# 90_51_4.net
KiCad netlist of a schematic drawn in Altium Designer
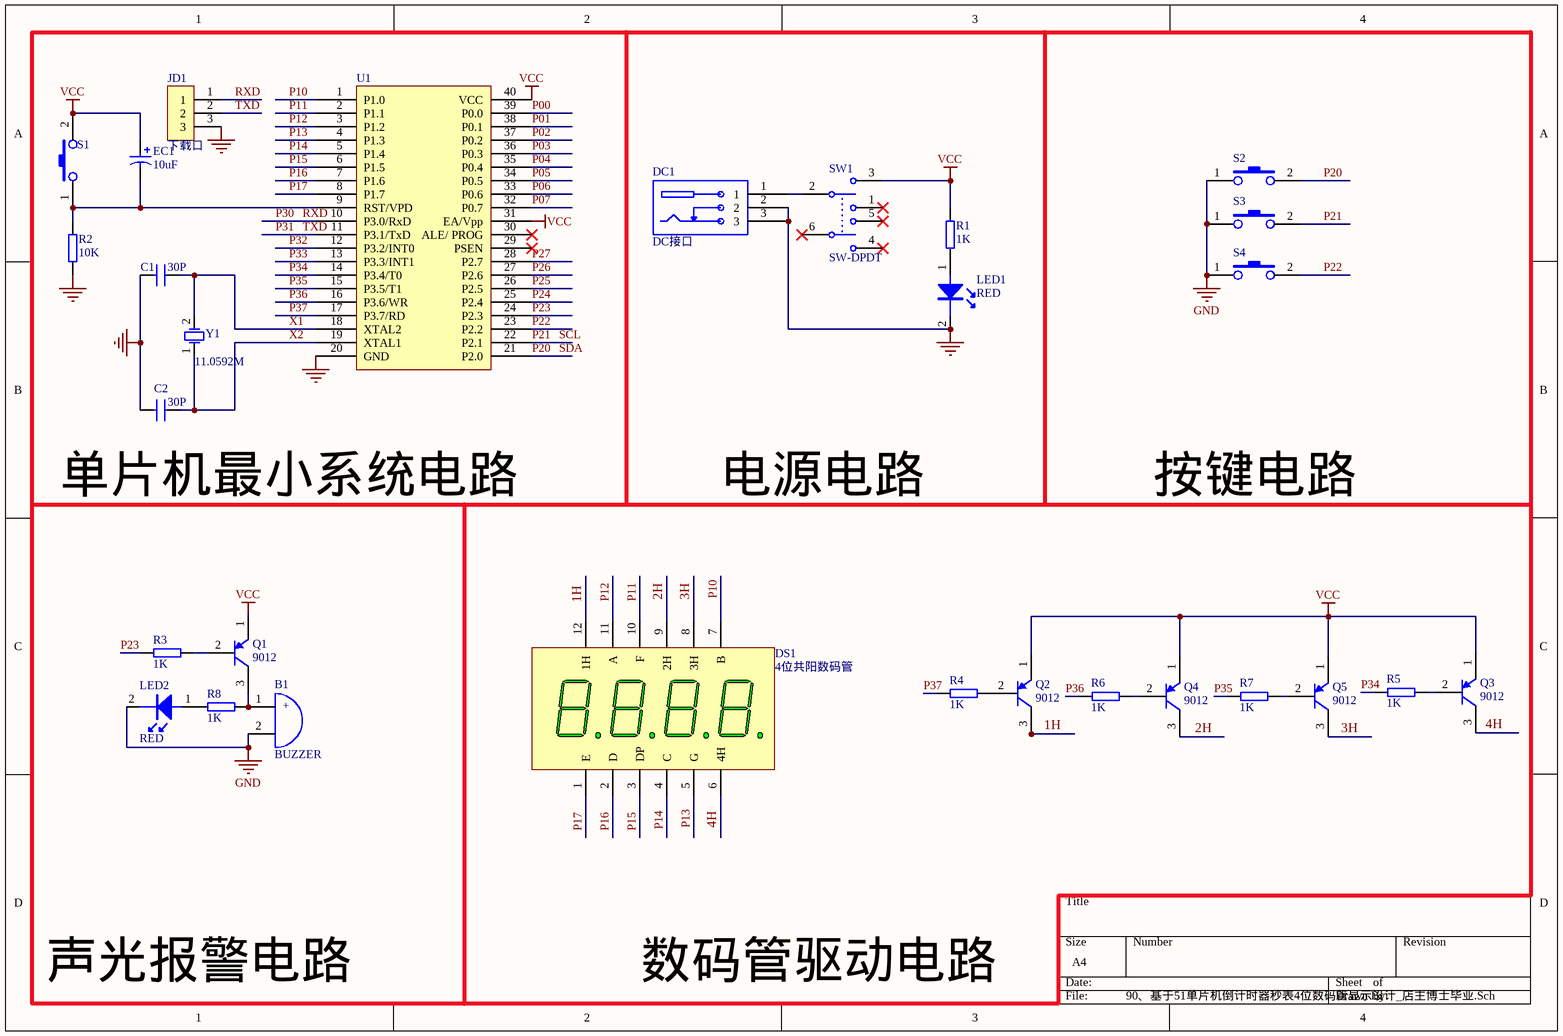
[diagram p0: 90、基于51单片机倒计时器秒表4位数码管显示设计_店主博士毕业.SchDoc]

(export (version "E")
  (design (tool "Eeschema 10.0.6"))
  (components
    (comp (ref "B1")
      (value "BUZZER")
      (footprint "BUZZERSOT_PLASTIC")
      (description "蜂鸣器")
      (libsource (lib "参考") (part "BUZZER"))
    )
    (comp (ref "C1")
      (value "30P")
      (footprint "RAD-0.1")
      (description "无极性电容")
      (libsource (lib "参考") (part "CAP"))
    )
    (comp (ref "C2")
      (value "30P")
      (footprint "RAD-0.1")
      (description "无极性电容")
      (libsource (lib "参考") (part "CAP"))
    )
    (comp (ref "DC1")
      (value "DC接口")
      (footprint "DC-JACK-002")
      (description "DC接口（分大小）")
      (libsource (lib "参考") (part "DC接口"))
    )
    (comp (ref "DS1") (value "4位共阳数码管") (footprint "SEG3641") (libsource (lib "参考") (part "4位共阳数码管")))
    (comp (ref "EC1")
      (value "10uF")
      (footprint "RB.1/.2")
      (description "极性电容")
      (libsource (lib "参考") (part "CAP_EC"))
    )
    (comp (ref "JD1")
      (value "下载口")
      (footprint "下载串口")
      (description "下载口2.54排针")
      (libsource (lib "参考") (part "下载口"))
    )
    (comp (ref "LED1")
      (value "RED")
      (footprint "LED_D3MM12")
      (description "LED灯")
      (libsource (lib "参考") (part "LED"))
    )
    (comp (ref "LED2")
      (value "RED")
      (footprint "LED_D3MM12")
      (description "LED灯")
      (libsource (lib "参考") (part "LED"))
    )
    (comp (ref "Q1")
      (value "9012")
      (footprint "TO-92")
      (description "直插三极管")
      (libsource (lib "参考") (part "9012"))
    )
    (comp (ref "Q2")
      (value "9012")
      (footprint "TO-92")
      (description "直插三极管")
      (libsource (lib "参考") (part "9012"))
    )
    (comp (ref "Q3")
      (value "9012")
      (footprint "TO-92")
      (description "直插三极管")
      (libsource (lib "参考") (part "9012"))
    )
    (comp (ref "Q4")
      (value "9012")
      (footprint "TO-92")
      (description "直插三极管")
      (libsource (lib "参考") (part "9012"))
    )
    (comp (ref "Q5")
      (value "9012")
      (footprint "TO-92")
      (description "直插三极管")
      (libsource (lib "参考") (part "9012"))
    )
    (comp (ref "R1")
      (value "1K")
      (footprint "AXIAL0.3")
      (description "电阻")
      (libsource (lib "参考") (part "RES"))
    )
    (comp (ref "R2")
      (value "10K")
      (footprint "AXIAL0.3")
      (description "电阻")
      (libsource (lib "参考") (part "RES"))
    )
    (comp (ref "R3")
      (value "1K")
      (footprint "AXIAL0.3")
      (description "电阻")
      (libsource (lib "参考") (part "RES"))
    )
    (comp (ref "R4")
      (value "1K")
      (footprint "AXIAL0.3")
      (description "电阻")
      (libsource (lib "参考") (part "RES"))
    )
    (comp (ref "R5")
      (value "1K")
      (footprint "AXIAL0.3")
      (description "电阻")
      (libsource (lib "参考") (part "RES"))
    )
    (comp (ref "R6")
      (value "1K")
      (footprint "AXIAL0.3")
      (description "电阻")
      (libsource (lib "参考") (part "RES"))
    )
    (comp (ref "R7")
      (value "1K")
      (footprint "AXIAL0.3")
      (description "电阻")
      (libsource (lib "参考") (part "RES"))
    )
    (comp (ref "R8")
      (value "1K")
      (footprint "AXIAL0.3")
      (description "电阻")
      (libsource (lib "参考") (part "RES"))
    )
    (comp (ref "S1")
      (value "BUTTOM")
      (footprint "BUTTOM_6x6DIP")
      (description "按键")
      (libsource (lib "参考") (part "BUTTOM"))
    )
    (comp (ref "S2")
      (value "BUTTOM")
      (footprint "BUTTOM_6x6DIP")
      (description "按键")
      (libsource (lib "参考") (part "BUTTOM"))
    )
    (comp (ref "S3")
      (value "BUTTOM")
      (footprint "BUTTOM_6x6DIP")
      (description "按键")
      (libsource (lib "参考") (part "BUTTOM"))
    )
    (comp (ref "S4")
      (value "BUTTOM")
      (footprint "BUTTOM_6x6DIP")
      (description "按键")
      (libsource (lib "参考") (part "BUTTOM"))
    )
    (comp (ref "SW1")
      (value "SW-DPDT")
      (footprint "SW")
      (description "电源开关")
      (fields (field (name "PUBLISHER") "Altium Limited"))
      (libsource (lib "参考") (part "SW-DPDT"))
    )
    (comp (ref "U1")
      (value "STC89C52")
      (footprint "STC89")
      (description "51单片机")
      (libsource (lib "参考") (part "STC51"))
    )
    (comp (ref "Y1")
      (value "11.0592M")
      (footprint "X_HC-49")
      (description "晶振")
      (libsource (lib "参考") (part "XTAL DIP"))
    )
  )
  (nets
    (net (code "1") (name "/1H") (class "Default")
      (node (ref "DS1") (pin "12") (pinfunction "1H_12") (pintype "passive"))
      (node (ref "Q2") (pin "3") (pinfunction "c_3") (pintype "passive"))
    )
    (net (code "2") (name "/2H") (class "Default")
      (node (ref "DS1") (pin "9") (pinfunction "2H_9") (pintype "passive"))
      (node (ref "Q4") (pin "3") (pinfunction "c_3") (pintype "passive"))
    )
    (net (code "3") (name "/3H") (class "Default")
      (node (ref "DS1") (pin "8") (pinfunction "3H_8") (pintype "passive"))
      (node (ref "Q5") (pin "3") (pinfunction "c_3") (pintype "passive"))
    )
    (net (code "4") (name "/4H") (class "Default")
      (node (ref "DS1") (pin "6") (pinfunction "4H_6") (pintype "passive"))
      (node (ref "Q3") (pin "3") (pinfunction "c_3") (pintype "passive"))
    )
    (net (code "5") (name "/P00") (class "Default")
      (node (ref "U1") (pin "39") (pinfunction "P0.0_39") (pintype "passive"))
    )
    (net (code "6") (name "/P01") (class "Default")
      (node (ref "U1") (pin "38") (pinfunction "P0.1_38") (pintype "passive"))
    )
    (net (code "7") (name "/P02") (class "Default")
      (node (ref "U1") (pin "37") (pinfunction "P0.2_37") (pintype "passive"))
    )
    (net (code "8") (name "/P03") (class "Default")
      (node (ref "U1") (pin "36") (pinfunction "P0.3_36") (pintype "passive"))
    )
    (net (code "9") (name "/P04") (class "Default")
      (node (ref "U1") (pin "35") (pinfunction "P0.4_35") (pintype "passive"))
    )
    (net (code "10") (name "/P05") (class "Default")
      (node (ref "U1") (pin "34") (pinfunction "P0.5_34") (pintype "passive"))
    )
    (net (code "11") (name "/P06") (class "Default")
      (node (ref "U1") (pin "33") (pinfunction "P0.6_33") (pintype "passive"))
    )
    (net (code "12") (name "/P07") (class "Default")
      (node (ref "U1") (pin "32") (pinfunction "P0.7_32") (pintype "passive"))
    )
    (net (code "13") (name "/P10") (class "Default")
      (node (ref "DS1") (pin "7") (pinfunction "B_7") (pintype "passive"))
      (node (ref "U1") (pin "1") (pinfunction "P1.0_1") (pintype "passive"))
    )
    (net (code "14") (name "/P11") (class "Default")
      (node (ref "DS1") (pin "10") (pinfunction "F_10") (pintype "passive"))
      (node (ref "U1") (pin "2") (pinfunction "P1.1_2") (pintype "passive"))
    )
    (net (code "15") (name "/P12") (class "Default")
      (node (ref "DS1") (pin "11") (pinfunction "A_11") (pintype "passive"))
      (node (ref "U1") (pin "3") (pinfunction "P1.2_3") (pintype "passive"))
    )
    (net (code "16") (name "/P13") (class "Default")
      (node (ref "DS1") (pin "5") (pinfunction "G_5") (pintype "passive"))
      (node (ref "U1") (pin "4") (pinfunction "P1.3_4") (pintype "passive"))
    )
    (net (code "17") (name "/P14") (class "Default")
      (node (ref "DS1") (pin "4") (pinfunction "C_4") (pintype "passive"))
      (node (ref "U1") (pin "5") (pinfunction "P1.4_5") (pintype "passive"))
    )
    (net (code "18") (name "/P15") (class "Default")
      (node (ref "DS1") (pin "3") (pinfunction "DP_3") (pintype "passive"))
      (node (ref "U1") (pin "6") (pinfunction "P1.5_6") (pintype "passive"))
    )
    (net (code "19") (name "/P16") (class "Default")
      (node (ref "DS1") (pin "2") (pinfunction "D_2") (pintype "passive"))
      (node (ref "U1") (pin "7") (pinfunction "P1.6_7") (pintype "passive"))
    )
    (net (code "20") (name "/P17") (class "Default")
      (node (ref "DS1") (pin "1") (pinfunction "E_1") (pintype "passive"))
      (node (ref "U1") (pin "8") (pinfunction "P1.7_8") (pintype "passive"))
    )
    (net (code "21") (name "/P20") (class "Default")
      (node (ref "S2") (pin "2") (pinfunction "2_2") (pintype "passive"))
      (node (ref "U1") (pin "21") (pinfunction "P2.0_21") (pintype "passive"))
    )
    (net (code "22") (name "/P21") (class "Default")
      (node (ref "S3") (pin "2") (pinfunction "2_2") (pintype "passive"))
      (node (ref "U1") (pin "22") (pinfunction "P2.1_22") (pintype "passive"))
    )
    (net (code "23") (name "/P22") (class "Default")
      (node (ref "S4") (pin "2") (pinfunction "2_2") (pintype "passive"))
      (node (ref "U1") (pin "23") (pinfunction "P2.2_23") (pintype "passive"))
    )
    (net (code "24") (name "/P23") (class "Default")
      (node (ref "R3") (pin "2") (pinfunction "2_2") (pintype "passive"))
      (node (ref "U1") (pin "24") (pinfunction "P2.3_24") (pintype "passive"))
    )
    (net (code "25") (name "/P24") (class "Default")
      (node (ref "U1") (pin "25") (pinfunction "P2.4_25") (pintype "passive"))
    )
    (net (code "26") (name "/P25") (class "Default")
      (node (ref "U1") (pin "26") (pinfunction "P2.5_26") (pintype "passive"))
    )
    (net (code "27") (name "/P26") (class "Default")
      (node (ref "U1") (pin "27") (pinfunction "P2.6_27") (pintype "passive"))
    )
    (net (code "28") (name "/P27") (class "Default")
      (node (ref "U1") (pin "28") (pinfunction "P2.7_28") (pintype "passive"))
    )
    (net (code "29") (name "/P30") (class "Default")
      (node (ref "JD1") (pin "1") (pinfunction "1_1") (pintype "passive"))
      (node (ref "U1") (pin "10") (pinfunction "P3.0/RxD_10") (pintype "passive"))
    )
    (net (code "30") (name "/P31") (class "Default")
      (node (ref "JD1") (pin "2") (pinfunction "2_2") (pintype "passive"))
      (node (ref "U1") (pin "11") (pinfunction "P3.1/TxD_11") (pintype "passive"))
    )
    (net (code "31") (name "/P32") (class "Default")
      (node (ref "U1") (pin "12") (pinfunction "P3.2/INT0_12") (pintype "passive"))
    )
    (net (code "32") (name "/P33") (class "Default")
      (node (ref "U1") (pin "13") (pinfunction "P3.3/INT1_13") (pintype "passive"))
    )
    (net (code "33") (name "/P34") (class "Default")
      (node (ref "R5") (pin "2") (pinfunction "2_2") (pintype "passive"))
      (node (ref "U1") (pin "14") (pinfunction "P3.4/T0_14") (pintype "passive"))
    )
    (net (code "34") (name "/P35") (class "Default")
      (node (ref "R7") (pin "2") (pinfunction "2_2") (pintype "passive"))
      (node (ref "U1") (pin "15") (pinfunction "P3.5/T1_15") (pintype "passive"))
    )
    (net (code "35") (name "/P36") (class "Default")
      (node (ref "R6") (pin "2") (pinfunction "2_2") (pintype "passive"))
      (node (ref "U1") (pin "16") (pinfunction "P3.6/WR_16") (pintype "passive"))
    )
    (net (code "36") (name "/P37") (class "Default")
      (node (ref "R4") (pin "2") (pinfunction "2_2") (pintype "passive"))
      (node (ref "U1") (pin "17") (pinfunction "P3.7/RD_17") (pintype "passive"))
    )
    (net (code "37") (name "/X1") (class "Default")
      (node (ref "C1") (pin "2") (pinfunction "2_2") (pintype "passive"))
      (node (ref "U1") (pin "18") (pinfunction "XTAL2_18") (pintype "passive"))
      (node (ref "Y1") (pin "2") (pinfunction "OSC2_2") (pintype "passive"))
    )
    (net (code "38") (name "/X2") (class "Default")
      (node (ref "C2") (pin "2") (pinfunction "2_2") (pintype "passive"))
      (node (ref "U1") (pin "19") (pinfunction "XTAL1_19") (pintype "passive"))
      (node (ref "Y1") (pin "1") (pinfunction "OSC1_1") (pintype "passive"))
    )
    (net (code "39") (name "GND") (class "Default")
      (node (ref "B1") (pin "2") (pinfunction "2_2") (pintype "passive"))
      (node (ref "C1") (pin "1") (pinfunction "1_1") (pintype "passive"))
      (node (ref "C2") (pin "1") (pinfunction "1_1") (pintype "passive"))
      (node (ref "DC1") (pin "2") (pinfunction "2_2") (pintype "passive"))
      (node (ref "DC1") (pin "3") (pinfunction "3_3") (pintype "passive"))
      (node (ref "JD1") (pin "3") (pinfunction "3_3") (pintype "passive"))
      (node (ref "LED1") (pin "2") (pinfunction "2_2") (pintype "passive"))
      (node (ref "LED2") (pin "2") (pinfunction "2_2") (pintype "passive"))
      (node (ref "R2") (pin "1") (pinfunction "1_1") (pintype "passive"))
      (node (ref "S2") (pin "1") (pinfunction "1_1") (pintype "passive"))
      (node (ref "S3") (pin "1") (pinfunction "1_1") (pintype "passive"))
      (node (ref "S4") (pin "1") (pinfunction "1_1") (pintype "passive"))
      (node (ref "U1") (pin "20") (pinfunction "GND_20") (pintype "passive"))
    )
    (net (code "40") (name "Net-(DC1-Pad1)") (class "Default")
      (node (ref "DC1") (pin "1") (pinfunction "1_1") (pintype "passive"))
      (node (ref "SW1") (pin "2") (pinfunction "2_2") (pintype "passive"))
    )
    (net (code "41") (name "Net-(LED1-Pad1)") (class "Default")
      (node (ref "LED1") (pin "1") (pinfunction "1_1") (pintype "passive"))
      (node (ref "R1") (pin "1") (pinfunction "1_1") (pintype "passive"))
    )
    (net (code "42") (name "Net-(LED2-Pad1)") (class "Default")
      (node (ref "LED2") (pin "1") (pinfunction "1_1") (pintype "passive"))
      (node (ref "R8") (pin "1") (pinfunction "1_1") (pintype "passive"))
    )
    (net (code "43") (name "Net-(Q1-b)") (class "Default")
      (node (ref "Q1") (pin "2") (pinfunction "b_2") (pintype "passive"))
      (node (ref "R3") (pin "1") (pinfunction "1_1") (pintype "passive"))
    )
    (net (code "44") (name "Net-(Q1-c)") (class "Default")
      (node (ref "B1") (pin "1") (pinfunction "1_1") (pintype "passive"))
      (node (ref "Q1") (pin "3") (pinfunction "c_3") (pintype "passive"))
      (node (ref "R8") (pin "2") (pinfunction "2_2") (pintype "passive"))
    )
    (net (code "45") (name "Net-(Q2-b)") (class "Default")
      (node (ref "Q2") (pin "2") (pinfunction "b_2") (pintype "passive"))
      (node (ref "R4") (pin "1") (pinfunction "1_1") (pintype "passive"))
    )
    (net (code "46") (name "Net-(Q3-b)") (class "Default")
      (node (ref "Q3") (pin "2") (pinfunction "b_2") (pintype "passive"))
      (node (ref "R5") (pin "1") (pinfunction "1_1") (pintype "passive"))
    )
    (net (code "47") (name "Net-(Q4-b)") (class "Default")
      (node (ref "Q4") (pin "2") (pinfunction "b_2") (pintype "passive"))
      (node (ref "R6") (pin "1") (pinfunction "1_1") (pintype "passive"))
    )
    (net (code "48") (name "Net-(Q5-b)") (class "Default")
      (node (ref "Q5") (pin "2") (pinfunction "b_2") (pintype "passive"))
      (node (ref "R7") (pin "1") (pinfunction "1_1") (pintype "passive"))
    )
    (net (code "49") (name "Net-(U1-RST{slash}VPD)") (class "Default")
      (node (ref "EC1") (pin "2") (pinfunction "2_2") (pintype "passive"))
      (node (ref "R2") (pin "2") (pinfunction "2_2") (pintype "passive"))
      (node (ref "S1") (pin "1") (pinfunction "1_1") (pintype "passive"))
      (node (ref "U1") (pin "9") (pinfunction "RST/VPD_9") (pintype "passive"))
    )
    (net (code "50") (name "VCC") (class "Default")
      (node (ref "EC1") (pin "1") (pinfunction "1_1") (pintype "passive"))
      (node (ref "Q1") (pin "1") (pinfunction "e_1") (pintype "passive"))
      (node (ref "Q2") (pin "1") (pinfunction "e_1") (pintype "passive"))
      (node (ref "Q3") (pin "1") (pinfunction "e_1") (pintype "passive"))
      (node (ref "Q4") (pin "1") (pinfunction "e_1") (pintype "passive"))
      (node (ref "Q5") (pin "1") (pinfunction "e_1") (pintype "passive"))
      (node (ref "R1") (pin "2") (pinfunction "2_2") (pintype "passive"))
      (node (ref "S1") (pin "2") (pinfunction "2_2") (pintype "passive"))
      (node (ref "SW1") (pin "3") (pinfunction "3_3") (pintype "passive"))
      (node (ref "U1") (pin "31") (pinfunction "EA/Vpp_31") (pintype "passive"))
      (node (ref "U1") (pin "40") (pinfunction "VCC_40") (pintype "passive"))
    )
    (net (code "51") (name "unconnected-(SW1-Pad1)") (class "Default")
      (node (ref "SW1") (pin "1") (pinfunction "1_1") (pintype "passive+no_connect"))
    )
    (net (code "52") (name "unconnected-(SW1-Pad4)") (class "Default")
      (node (ref "SW1") (pin "4") (pinfunction "4_4") (pintype "passive+no_connect"))
    )
    (net (code "53") (name "unconnected-(SW1-Pad5)") (class "Default")
      (node (ref "SW1") (pin "5") (pinfunction "5_5") (pintype "passive+no_connect"))
    )
    (net (code "54") (name "unconnected-(SW1-Pad6)") (class "Default")
      (node (ref "SW1") (pin "6") (pinfunction "6_6") (pintype "passive+no_connect"))
    )
    (net (code "55") (name "unconnected-(U1-ALE{slash}_PROG-Pad30)") (class "Default")
      (node (ref "U1") (pin "30") (pinfunction "ALE/_PROG_30") (pintype "passive+no_connect"))
    )
    (net (code "56") (name "unconnected-(U1-PSEN-Pad29)") (class "Default")
      (node (ref "U1") (pin "29") (pinfunction "PSEN_29") (pintype "passive+no_connect"))
    )
  )
)
